# First32.net
KiCad netlist of a schematic drawn in Altium Designer
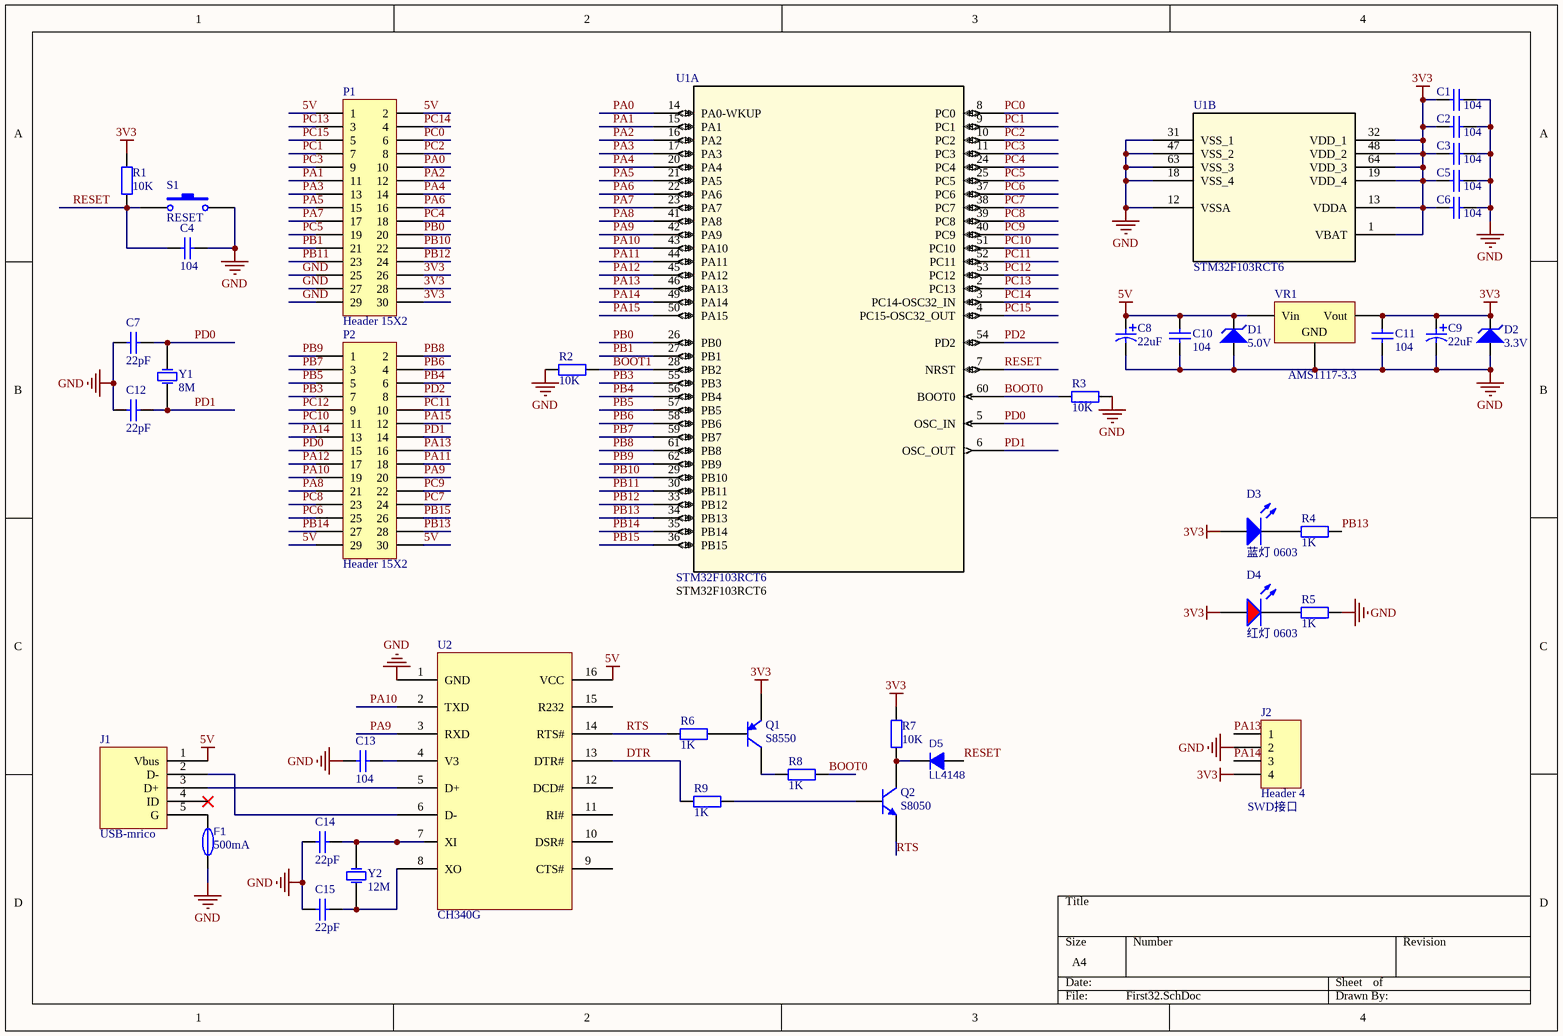
[diagram p0: First32.SchDoc]

(export (version "E")
  (design (tool "Eeschema 10.0.6"))
  (components
    (comp (ref "C1")
      (value "104")
      (footprint "0603_C")
      (description "贴片电容")
      (fields (field (name "Comment") "100nF (104) 10% 50V"))
      (libsource (lib "First32") (part "0603 100nF (104) 10% 50V"))
    )
    (comp (ref "C2")
      (value "104")
      (footprint "0603_C")
      (description "贴片电容")
      (fields (field (name "Comment") "100nF (104) 10% 50V"))
      (libsource (lib "First32") (part "0603 100nF (104) 10% 50V"))
    )
    (comp (ref "C3")
      (value "104")
      (footprint "0603_C")
      (description "贴片电容")
      (fields (field (name "Comment") "100nF (104) 10% 50V"))
      (libsource (lib "First32") (part "0603 100nF (104) 10% 50V"))
    )
    (comp (ref "C4")
      (value "104")
      (footprint "0603_C")
      (description "贴片电容")
      (fields (field (name "Comment") "100nF (104) 10% 50V"))
      (libsource (lib "First32") (part "0603 100nF (104) 10% 50V"))
    )
    (comp (ref "C5")
      (value "104")
      (footprint "0603_C")
      (description "贴片电容")
      (fields (field (name "Comment") "100nF (104) 10% 50V"))
      (libsource (lib "First32") (part "0603 100nF (104) 10% 50V"))
    )
    (comp (ref "C6")
      (value "104")
      (footprint "0603_C")
      (description "贴片电容")
      (fields (field (name "Comment") "100nF (104) 10% 50V"))
      (libsource (lib "First32") (part "0603 100nF (104) 10% 50V"))
    )
    (comp (ref "C7")
      (value "22pF")
      (footprint "0603_C")
      (description "贴片电容")
      (fields (field (name "Comment") "22pF (220) 5% 50V"))
      (libsource (lib "First32") (part "0603 22pF (220) 5% 50V"))
    )
    (comp (ref "C8")
      (value "22uF")
      (footprint "CASE-B_3528")
      (description "钽电容")
      (fields (field (name "Comment") "22uF(226) 10% 16V"))
      (libsource (lib "First32") (part "3528 22uF(226) 10% 16V"))
    )
    (comp (ref "C9")
      (value "22uF")
      (footprint "CASE-B_3528")
      (description "钽电容")
      (fields (field (name "Comment") "22uF(226) 10% 16V"))
      (libsource (lib "First32") (part "3528 22uF(226) 10% 16V"))
    )
    (comp (ref "C10")
      (value "104")
      (footprint "0603_C")
      (description "贴片电容")
      (fields (field (name "Comment") "100nF (104) 10% 50V"))
      (libsource (lib "First32") (part "0603 100nF (104) 10% 50V"))
    )
    (comp (ref "C11")
      (value "104")
      (footprint "0603_C")
      (description "贴片电容")
      (fields (field (name "Comment") "100nF (104) 10% 50V"))
      (libsource (lib "First32") (part "0603 100nF (104) 10% 50V"))
    )
    (comp (ref "C12")
      (value "22pF")
      (footprint "0603_C")
      (description "贴片电容")
      (fields (field (name "Comment") "22pF (220) 5% 50V"))
      (libsource (lib "First32") (part "0603 22pF (220) 5% 50V"))
    )
    (comp (ref "C13")
      (value "104")
      (footprint "0603_C")
      (description "贴片电容")
      (fields (field (name "Comment") "100nF (104) 10% 50V"))
      (libsource (lib "First32") (part "0603 100nF (104) 10% 50V"))
    )
    (comp (ref "C14")
      (value "22pF")
      (footprint "0603_C")
      (description "贴片电容")
      (fields (field (name "Comment") "22pF (220) 5% 50V"))
      (libsource (lib "First32") (part "0603 22pF (220) 5% 50V"))
    )
    (comp (ref "C15")
      (value "22pF")
      (footprint "0603_C")
      (description "贴片电容")
      (fields (field (name "Comment") "22pF (220) 5% 50V"))
      (libsource (lib "First32") (part "0603 22pF (220) 5% 50V"))
    )
    (comp (ref "D1")
      (value "5.0V")
      (footprint "SOD-123")
      (description "稳压二极管")
      (fields (field (name "Comment") "5V"))
      (libsource (lib "First32") (part "Diode-Zener"))
    )
    (comp (ref "D2")
      (value "3.3V")
      (footprint "SOD-123")
      (description "稳压二极管")
      (fields (field (name "Comment") "5V"))
      (libsource (lib "First32") (part "Diode-Zener"))
    )
    (comp (ref "D3")
      (value "蓝灯 0603")
      (footprint "0603_LED")
      (description "发光二极管")
      (libsource (lib "First32") (part "0603 蓝灯"))
    )
    (comp (ref "D4")
      (value "红灯 0603")
      (footprint "0603_LED")
      (description "发光二极管")
      (libsource (lib "First32") (part "0603 红灯"))
    )
    (comp (ref "D5")
      (value "LL4148")
      (footprint "LL-34")
      (fields (field (name "BOM_SUPPLIER PART") "C9808"))
      (libsource (lib "First32") (part "LL4148"))
    )
    (comp (ref "F1")
      (value "500mA")
      (footprint "0805_F")
      (description "保险")
      (fields
        (field (name "BOM_SUPPLIER PART") "C261942")
        (field (name "BOM_MANUFACTURER PART") "TLC-PSMD050")
        (field (name "CONTRIBUTOR") "LCSC")
      )
      (libsource (lib "First32") (part "Fuse"))
    )
    (comp (ref "J1")
      (value "USB-mrico")
      (footprint "SMD-USB-micro_B")
      (libsource (lib "First32") (part "Micro_USB_B"))
    )
    (comp (ref "J2")
      (value "Header 4")
      (footprint "HDR 1X4")
      (description "Header, 4-Pin")
      (fields (field (name "ALTIUM_VALUE") "SWD接口") (field (name "PUBLISHER") "Altium Limited"))
      (libsource (lib "First32") (part "Header 4"))
    )
    (comp (ref "P1")
      (value "Header 15X2")
      (footprint "HDR 2x15 2.54 mm")
      (description "Header, 15-Pin, Dual row")
      (fields (field (name "PUBLISHER") "Altium Limited"))
      (libsource (lib "First32") (part "Header 15X2"))
    )
    (comp (ref "P2")
      (value "Header 15X2")
      (footprint "HDR 2x15 2.54 mm")
      (description "Header, 15-Pin, Dual row")
      (fields (field (name "PUBLISHER") "Altium Limited"))
      (libsource (lib "First32") (part "Header 15X2"))
    )
    (comp (ref "Q1")
      (value "S8550")
      (footprint "SOT-23")
      (description "PNP三极管")
      (fields (field (name "PUBLISHER") "Altium Limited"))
      (libsource (lib "First32") (part "S8550"))
    )
    (comp (ref "Q2")
      (value "S8050")
      (footprint "SOT-23")
      (description "NPN三极管")
      (libsource (lib "First32") (part "S8050"))
    )
    (comp (ref "R1")
      (value "10K")
      (footprint "0603_R")
      (description "贴片电阻")
      (libsource (lib "First32") (part "0603 10KΩ (1002) 1%"))
    )
    (comp (ref "R2")
      (value "10K")
      (footprint "0603_R")
      (description "贴片电阻")
      (libsource (lib "") (part "0603 10KΩ (1002) 1%_2"))
    )
    (comp (ref "R3")
      (value "10K")
      (footprint "0603_R")
      (description "贴片电阻")
      (libsource (lib "") (part "0603 10KΩ (1002) 1%_1"))
    )
    (comp (ref "R4")
      (value "1K")
      (footprint "0603_R")
      (description "贴片电阻")
      (libsource (lib "First32") (part "0603 1KΩ (1K) 1%"))
    )
    (comp (ref "R5")
      (value "1K")
      (footprint "0603_R")
      (description "贴片电阻")
      (libsource (lib "First32") (part "0603 1KΩ (1K) 1%"))
    )
    (comp (ref "R6")
      (value "1K")
      (footprint "0603_R")
      (description "贴片电阻")
      (libsource (lib "First32") (part "0603 1KΩ (1K) 1%"))
    )
    (comp (ref "R7")
      (value "10K")
      (footprint "0603_R")
      (description "贴片电阻")
      (libsource (lib "First32") (part "0603 10KΩ (1002) 1%"))
    )
    (comp (ref "R8")
      (value "1K")
      (footprint "0603_R")
      (description "贴片电阻")
      (libsource (lib "First32") (part "0603 1KΩ (1K) 1%"))
    )
    (comp (ref "R9")
      (value "1K")
      (footprint "0603_R")
      (description "贴片电阻")
      (libsource (lib "First32") (part "0603 1KΩ (1K) 1%"))
    )
    (comp (ref "S1")
      (value "RESET")
      (footprint "SW-SMD-4*4")
      (description "4脚按键")
      (fields (field (name "PUBLISHER") "LC"))
      (libsource (lib "First32") (part "SW-PB-4P"))
    )
    (comp (ref "U1")
      (value "STM32F103RCT6")
      (footprint "LQFP64-10x10mm")
      (description "No Description Available")
      (fields
        (field (name "MANUFACTURER_PART_NUMBER") "STM32F103RCT6")
        (field (name "COPYRIGHT") "Copyright (C) 2018 Accelerated Designs. All rights reserved")
      )
      (libsource (lib "First32") (part "STM32F103RCT6"))
    )
    (comp (ref "U2") (value "CH340G") (footprint "SOP-16_150mil") (libsource (lib "First32") (part "CH340G")))
    (comp (ref "VR1")
      (value "AMS1117-3.3")
      (footprint "SOT-223")
      (description "低压差线性稳压(LDO)")
      (libsource (lib "First32") (part "SOT-223 AMS1117-3.3"))
    )
    (comp (ref "Y1")
      (value "8M")
      (footprint "HC-49SMD")
      (description "Crystal Oscillator")
      (fields (field (name "Comment") "XTAL") (field (name "PUBLISHER") "Altium Limited"))
      (libsource (lib "First32") (part "XTAL"))
    )
    (comp (ref "Y2")
      (value "12M")
      (footprint "HC-49S_L11.4-W4.8")
      (description "Crystal Oscillator")
      (fields (field (name "Comment") "XTAL") (field (name "PUBLISHER") "Altium Limited"))
      (libsource (lib "First32") (part "XTAL_12M"))
    )
  )
  (nets
    (net (code "1") (name "/BOOT0") (class "Default")
      (node (ref "R3") (pin "2") (pinfunction "2_2") (pintype "passive"))
      (node (ref "R8") (pin "2") (pinfunction "2_2") (pintype "passive"))
      (node (ref "U1") (pin "60") (pinfunction "BOOT0_60") (pintype "input"))
    )
    (net (code "2") (name "/BOOT1") (class "Default")
      (node (ref "R2") (pin "2") (pinfunction "2_2") (pintype "passive"))
      (node (ref "U1") (pin "28") (pinfunction "PB2_28") (pintype "bidirectional"))
    )
    (net (code "3") (name "/DTR") (class "Default")
      (node (ref "R9") (pin "1") (pinfunction "1_1") (pintype "passive"))
      (node (ref "U2") (pin "13") (pinfunction "DTR#_13") (pintype "passive"))
    )
    (net (code "4") (name "/PA0") (class "Default")
      (node (ref "P1") (pin "10") (pinfunction "10_10") (pintype "passive"))
      (node (ref "U1") (pin "14") (pinfunction "PA0-WKUP_14") (pintype "bidirectional"))
    )
    (net (code "5") (name "/PA1") (class "Default")
      (node (ref "P1") (pin "11") (pinfunction "11_11") (pintype "passive"))
      (node (ref "U1") (pin "15") (pinfunction "PA1_15") (pintype "bidirectional"))
    )
    (net (code "6") (name "/PA2") (class "Default")
      (node (ref "P1") (pin "12") (pinfunction "12_12") (pintype "passive"))
      (node (ref "U1") (pin "16") (pinfunction "PA2_16") (pintype "bidirectional"))
    )
    (net (code "7") (name "/PA3") (class "Default")
      (node (ref "P1") (pin "13") (pinfunction "13_13") (pintype "passive"))
      (node (ref "U1") (pin "17") (pinfunction "PA3_17") (pintype "bidirectional"))
    )
    (net (code "8") (name "/PA4") (class "Default")
      (node (ref "P1") (pin "14") (pinfunction "14_14") (pintype "passive"))
      (node (ref "U1") (pin "20") (pinfunction "PA4_20") (pintype "bidirectional"))
    )
    (net (code "9") (name "/PA5") (class "Default")
      (node (ref "P1") (pin "15") (pinfunction "15_15") (pintype "passive"))
      (node (ref "U1") (pin "21") (pinfunction "PA5_21") (pintype "bidirectional"))
    )
    (net (code "10") (name "/PA6") (class "Default")
      (node (ref "P1") (pin "16") (pinfunction "16_16") (pintype "passive"))
      (node (ref "U1") (pin "22") (pinfunction "PA6_22") (pintype "bidirectional"))
    )
    (net (code "11") (name "/PA7") (class "Default")
      (node (ref "P1") (pin "17") (pinfunction "17_17") (pintype "passive"))
      (node (ref "U1") (pin "23") (pinfunction "PA7_23") (pintype "bidirectional"))
    )
    (net (code "12") (name "/PA8") (class "Default")
      (node (ref "P2") (pin "21") (pinfunction "21_21") (pintype "passive"))
      (node (ref "U1") (pin "41") (pinfunction "PA8_41") (pintype "bidirectional"))
    )
    (net (code "13") (name "/PA9") (class "Default")
      (node (ref "P2") (pin "20") (pinfunction "20_20") (pintype "passive"))
      (node (ref "U1") (pin "42") (pinfunction "PA9_42") (pintype "bidirectional"))
      (node (ref "U2") (pin "3") (pinfunction "RXD_3") (pintype "passive"))
    )
    (net (code "14") (name "/PA10") (class "Default")
      (node (ref "P2") (pin "19") (pinfunction "19_19") (pintype "passive"))
      (node (ref "U1") (pin "43") (pinfunction "PA10_43") (pintype "bidirectional"))
      (node (ref "U2") (pin "2") (pinfunction "TXD_2") (pintype "passive"))
    )
    (net (code "15") (name "/PA11") (class "Default")
      (node (ref "P2") (pin "18") (pinfunction "18_18") (pintype "passive"))
      (node (ref "U1") (pin "44") (pinfunction "PA11_44") (pintype "bidirectional"))
    )
    (net (code "16") (name "/PA12") (class "Default")
      (node (ref "P2") (pin "17") (pinfunction "17_17") (pintype "passive"))
      (node (ref "U1") (pin "45") (pinfunction "PA12_45") (pintype "bidirectional"))
    )
    (net (code "17") (name "/PA13") (class "Default")
      (node (ref "J2") (pin "1") (pinfunction "1_1") (pintype "passive"))
      (node (ref "P2") (pin "16") (pinfunction "16_16") (pintype "passive"))
      (node (ref "U1") (pin "46") (pinfunction "PA13_46") (pintype "bidirectional"))
    )
    (net (code "18") (name "/PA14") (class "Default")
      (node (ref "J2") (pin "3") (pinfunction "3_3") (pintype "passive"))
      (node (ref "P2") (pin "13") (pinfunction "13_13") (pintype "passive"))
      (node (ref "U1") (pin "49") (pinfunction "PA14_49") (pintype "bidirectional"))
    )
    (net (code "19") (name "/PA15") (class "Default")
      (node (ref "P2") (pin "12") (pinfunction "12_12") (pintype "passive"))
      (node (ref "U1") (pin "50") (pinfunction "PA15_50") (pintype "bidirectional"))
    )
    (net (code "20") (name "/PB0") (class "Default")
      (node (ref "P1") (pin "20") (pinfunction "20_20") (pintype "passive"))
      (node (ref "U1") (pin "26") (pinfunction "PB0_26") (pintype "bidirectional"))
    )
    (net (code "21") (name "/PB1") (class "Default")
      (node (ref "P1") (pin "21") (pinfunction "21_21") (pintype "passive"))
      (node (ref "U1") (pin "27") (pinfunction "PB1_27") (pintype "bidirectional"))
    )
    (net (code "22") (name "/PB3") (class "Default")
      (node (ref "P2") (pin "7") (pinfunction "7_7") (pintype "passive"))
      (node (ref "U1") (pin "55") (pinfunction "PB3_55") (pintype "bidirectional"))
    )
    (net (code "23") (name "/PB4") (class "Default")
      (node (ref "P2") (pin "6") (pinfunction "6_6") (pintype "passive"))
      (node (ref "U1") (pin "56") (pinfunction "PB4_56") (pintype "bidirectional"))
    )
    (net (code "24") (name "/PB5") (class "Default")
      (node (ref "P2") (pin "5") (pinfunction "5_5") (pintype "passive"))
      (node (ref "U1") (pin "57") (pinfunction "PB5_57") (pintype "bidirectional"))
    )
    (net (code "25") (name "/PB6") (class "Default")
      (node (ref "P2") (pin "4") (pinfunction "4_4") (pintype "passive"))
      (node (ref "U1") (pin "58") (pinfunction "PB6_58") (pintype "bidirectional"))
    )
    (net (code "26") (name "/PB7") (class "Default")
      (node (ref "P2") (pin "3") (pinfunction "3_3") (pintype "passive"))
      (node (ref "U1") (pin "59") (pinfunction "PB7_59") (pintype "bidirectional"))
    )
    (net (code "27") (name "/PB8") (class "Default")
      (node (ref "P2") (pin "2") (pinfunction "2_2") (pintype "passive"))
      (node (ref "U1") (pin "61") (pinfunction "PB8_61") (pintype "bidirectional"))
    )
    (net (code "28") (name "/PB9") (class "Default")
      (node (ref "P2") (pin "1") (pinfunction "1_1") (pintype "passive"))
      (node (ref "U1") (pin "62") (pinfunction "PB9_62") (pintype "bidirectional"))
    )
    (net (code "29") (name "/PB10") (class "Default")
      (node (ref "P1") (pin "22") (pinfunction "22_22") (pintype "passive"))
      (node (ref "U1") (pin "29") (pinfunction "PB10_29") (pintype "bidirectional"))
    )
    (net (code "30") (name "/PB11") (class "Default")
      (node (ref "P1") (pin "23") (pinfunction "23_23") (pintype "passive"))
      (node (ref "U1") (pin "30") (pinfunction "PB11_30") (pintype "bidirectional"))
    )
    (net (code "31") (name "/PB12") (class "Default")
      (node (ref "P1") (pin "24") (pinfunction "24_24") (pintype "passive"))
      (node (ref "U1") (pin "33") (pinfunction "PB12_33") (pintype "bidirectional"))
    )
    (net (code "32") (name "/PB13") (class "Default")
      (node (ref "P2") (pin "28") (pinfunction "28_28") (pintype "passive"))
      (node (ref "R4") (pin "2") (pinfunction "2_2") (pintype "passive"))
      (node (ref "U1") (pin "34") (pinfunction "PB13_34") (pintype "bidirectional"))
    )
    (net (code "33") (name "/PB14") (class "Default")
      (node (ref "P2") (pin "27") (pinfunction "27_27") (pintype "passive"))
      (node (ref "U1") (pin "35") (pinfunction "PB14_35") (pintype "bidirectional"))
    )
    (net (code "34") (name "/PB15") (class "Default")
      (node (ref "P2") (pin "26") (pinfunction "26_26") (pintype "passive"))
      (node (ref "U1") (pin "36") (pinfunction "PB15_36") (pintype "bidirectional"))
    )
    (net (code "35") (name "/PC0") (class "Default")
      (node (ref "P1") (pin "6") (pinfunction "6_6") (pintype "passive"))
      (node (ref "U1") (pin "8") (pinfunction "PC0_8") (pintype "bidirectional"))
    )
    (net (code "36") (name "/PC1") (class "Default")
      (node (ref "P1") (pin "7") (pinfunction "7_7") (pintype "passive"))
      (node (ref "U1") (pin "9") (pinfunction "PC1_9") (pintype "bidirectional"))
    )
    (net (code "37") (name "/PC2") (class "Default")
      (node (ref "P1") (pin "8") (pinfunction "8_8") (pintype "passive"))
      (node (ref "U1") (pin "10") (pinfunction "PC2_10") (pintype "bidirectional"))
    )
    (net (code "38") (name "/PC3") (class "Default")
      (node (ref "P1") (pin "9") (pinfunction "9_9") (pintype "passive"))
      (node (ref "U1") (pin "11") (pinfunction "PC3_11") (pintype "bidirectional"))
    )
    (net (code "39") (name "/PC4") (class "Default")
      (node (ref "P1") (pin "18") (pinfunction "18_18") (pintype "passive"))
      (node (ref "U1") (pin "24") (pinfunction "PC4_24") (pintype "bidirectional"))
    )
    (net (code "40") (name "/PC5") (class "Default")
      (node (ref "P1") (pin "19") (pinfunction "19_19") (pintype "passive"))
      (node (ref "U1") (pin "25") (pinfunction "PC5_25") (pintype "bidirectional"))
    )
    (net (code "41") (name "/PC6") (class "Default")
      (node (ref "P2") (pin "25") (pinfunction "25_25") (pintype "passive"))
      (node (ref "U1") (pin "37") (pinfunction "PC6_37") (pintype "bidirectional"))
    )
    (net (code "42") (name "/PC7") (class "Default")
      (node (ref "P2") (pin "24") (pinfunction "24_24") (pintype "passive"))
      (node (ref "U1") (pin "38") (pinfunction "PC7_38") (pintype "bidirectional"))
    )
    (net (code "43") (name "/PC8") (class "Default")
      (node (ref "P2") (pin "23") (pinfunction "23_23") (pintype "passive"))
      (node (ref "U1") (pin "39") (pinfunction "PC8_39") (pintype "bidirectional"))
    )
    (net (code "44") (name "/PC9") (class "Default")
      (node (ref "P2") (pin "22") (pinfunction "22_22") (pintype "passive"))
      (node (ref "U1") (pin "40") (pinfunction "PC9_40") (pintype "bidirectional"))
    )
    (net (code "45") (name "/PC10") (class "Default")
      (node (ref "P2") (pin "11") (pinfunction "11_11") (pintype "passive"))
      (node (ref "U1") (pin "51") (pinfunction "PC10_51") (pintype "bidirectional"))
    )
    (net (code "46") (name "/PC11") (class "Default")
      (node (ref "P2") (pin "10") (pinfunction "10_10") (pintype "passive"))
      (node (ref "U1") (pin "52") (pinfunction "PC11_52") (pintype "bidirectional"))
    )
    (net (code "47") (name "/PC12") (class "Default")
      (node (ref "P2") (pin "9") (pinfunction "9_9") (pintype "passive"))
      (node (ref "U1") (pin "53") (pinfunction "PC12_53") (pintype "bidirectional"))
    )
    (net (code "48") (name "/PC13") (class "Default")
      (node (ref "P1") (pin "3") (pinfunction "3_3") (pintype "passive"))
      (node (ref "U1") (pin "2") (pinfunction "PC13_2") (pintype "bidirectional"))
    )
    (net (code "49") (name "/PC14") (class "Default")
      (node (ref "P1") (pin "4") (pinfunction "4_4") (pintype "passive"))
      (node (ref "U1") (pin "3") (pinfunction "PC14-OSC32_IN_3") (pintype "bidirectional"))
    )
    (net (code "50") (name "/PC15") (class "Default")
      (node (ref "P1") (pin "5") (pinfunction "5_5") (pintype "passive"))
      (node (ref "U1") (pin "4") (pinfunction "PC15-OSC32_OUT_4") (pintype "bidirectional"))
    )
    (net (code "51") (name "/PD0") (class "Default")
      (node (ref "C7") (pin "2") (pinfunction "2_2") (pintype "passive"))
      (node (ref "P2") (pin "15") (pinfunction "15_15") (pintype "passive"))
      (node (ref "U1") (pin "5") (pinfunction "OSC_IN_5") (pintype "input"))
      (node (ref "Y1") (pin "2") (pinfunction "OSC2_2") (pintype "passive"))
    )
    (net (code "52") (name "/PD1") (class "Default")
      (node (ref "C12") (pin "2") (pinfunction "2_2") (pintype "passive"))
      (node (ref "P2") (pin "14") (pinfunction "14_14") (pintype "passive"))
      (node (ref "U1") (pin "6") (pinfunction "OSC_OUT_6") (pintype "output"))
      (node (ref "Y1") (pin "1") (pinfunction "OSC1_1") (pintype "passive"))
    )
    (net (code "53") (name "/PD2") (class "Default")
      (node (ref "P2") (pin "8") (pinfunction "8_8") (pintype "passive"))
      (node (ref "U1") (pin "54") (pinfunction "PD2_54") (pintype "bidirectional"))
    )
    (net (code "54") (name "/RESET") (class "Default")
      (node (ref "C4") (pin "1") (pinfunction "1_1") (pintype "passive"))
      (node (ref "D5") (pin "1") (pinfunction "A_1") (pintype "passive"))
      (node (ref "R1") (pin "1") (pinfunction "1_1") (pintype "passive"))
      (node (ref "S1") (pin "1") (pinfunction "1_1") (pintype "passive"))
      (node (ref "U1") (pin "7") (pinfunction "NRST_7") (pintype "bidirectional"))
    )
    (net (code "55") (name "/RTS") (class "Default")
      (node (ref "Q2") (pin "2") (pinfunction "E_2") (pintype "passive"))
      (node (ref "R6") (pin "1") (pinfunction "1_1") (pintype "passive"))
      (node (ref "U2") (pin "14") (pinfunction "RTS#_14") (pintype "passive"))
    )
    (net (code "56") (name "3V3") (class "Default")
      (node (ref "C1") (pin "1") (pinfunction "1_1") (pintype "passive"))
      (node (ref "C11") (pin "1") (pinfunction "1_1") (pintype "passive"))
      (node (ref "C2") (pin "1") (pinfunction "1_1") (pintype "passive"))
      (node (ref "C3") (pin "1") (pinfunction "1_1") (pintype "passive"))
      (node (ref "C5") (pin "1") (pinfunction "1_1") (pintype "passive"))
      (node (ref "C6") (pin "1") (pinfunction "1_1") (pintype "passive"))
      (node (ref "C9") (pin "1") (pinfunction "1_1") (pintype "passive"))
      (node (ref "D2") (pin "1") (pinfunction "K_1") (pintype "passive"))
      (node (ref "D3") (pin "A") (pinfunction "A_A") (pintype "passive"))
      (node (ref "D4") (pin "A") (pinfunction "A_A") (pintype "passive"))
      (node (ref "J2") (pin "4") (pinfunction "4_4") (pintype "passive"))
      (node (ref "P1") (pin "26") (pinfunction "26_26") (pintype "passive"))
      (node (ref "P1") (pin "28") (pinfunction "28_28") (pintype "passive"))
      (node (ref "P1") (pin "30") (pinfunction "30_30") (pintype "passive"))
      (node (ref "Q1") (pin "2") (pinfunction "E_2") (pintype "passive"))
      (node (ref "R1") (pin "2") (pinfunction "2_2") (pintype "passive"))
      (node (ref "R7") (pin "2") (pinfunction "2_2") (pintype "passive"))
      (node (ref "U1") (pin "1") (pinfunction "VBAT_1") (pintype "power_in"))
      (node (ref "U1") (pin "13") (pinfunction "VDDA_13") (pintype "power_in"))
      (node (ref "U1") (pin "19") (pinfunction "VDD_4_19") (pintype "power_in"))
      (node (ref "U1") (pin "32") (pinfunction "VDD_1_32") (pintype "power_in"))
      (node (ref "U1") (pin "48") (pinfunction "VDD_2_48") (pintype "power_in"))
      (node (ref "U1") (pin "64") (pinfunction "VDD_3_64") (pintype "power_in"))
      (node (ref "VR1") (pin "2") (pinfunction "Vout_2") (pintype "passive"))
    )
    (net (code "57") (name "5V") (class "Default")
      (node (ref "C10") (pin "1") (pinfunction "1_1") (pintype "passive"))
      (node (ref "C8") (pin "1") (pinfunction "1_1") (pintype "passive"))
      (node (ref "D1") (pin "1") (pinfunction "K_1") (pintype "passive"))
      (node (ref "J1") (pin "1") (pinfunction "Vbus_1") (pintype "passive"))
      (node (ref "P1") (pin "1") (pinfunction "1_1") (pintype "passive"))
      (node (ref "P1") (pin "2") (pinfunction "2_2") (pintype "passive"))
      (node (ref "P2") (pin "29") (pinfunction "29_29") (pintype "passive"))
      (node (ref "P2") (pin "30") (pinfunction "30_30") (pintype "passive"))
      (node (ref "U2") (pin "16") (pinfunction "VCC_16") (pintype "passive"))
      (node (ref "VR1") (pin "3") (pinfunction "Vin_3") (pintype "passive"))
    )
    (net (code "58") (name "GND") (class "Default")
      (node (ref "C1") (pin "2") (pinfunction "2_2") (pintype "passive"))
      (node (ref "C10") (pin "2") (pinfunction "2_2") (pintype "passive"))
      (node (ref "C11") (pin "2") (pinfunction "2_2") (pintype "passive"))
      (node (ref "C12") (pin "1") (pinfunction "1_1") (pintype "passive"))
      (node (ref "C13") (pin "1") (pinfunction "1_1") (pintype "passive"))
      (node (ref "C14") (pin "1") (pinfunction "1_1") (pintype "passive"))
      (node (ref "C15") (pin "1") (pinfunction "1_1") (pintype "passive"))
      (node (ref "C2") (pin "2") (pinfunction "2_2") (pintype "passive"))
      (node (ref "C3") (pin "2") (pinfunction "2_2") (pintype "passive"))
      (node (ref "C4") (pin "2") (pinfunction "2_2") (pintype "passive"))
      (node (ref "C5") (pin "2") (pinfunction "2_2") (pintype "passive"))
      (node (ref "C6") (pin "2") (pinfunction "2_2") (pintype "passive"))
      (node (ref "C7") (pin "1") (pinfunction "1_1") (pintype "passive"))
      (node (ref "C8") (pin "2") (pinfunction "2_2") (pintype "passive"))
      (node (ref "C9") (pin "2") (pinfunction "2_2") (pintype "passive"))
      (node (ref "D1") (pin "2") (pinfunction "A_2") (pintype "passive"))
      (node (ref "D2") (pin "2") (pinfunction "A_2") (pintype "passive"))
      (node (ref "F1") (pin "1") (pinfunction "1_1") (pintype "passive"))
      (node (ref "J2") (pin "2") (pinfunction "2_2") (pintype "passive"))
      (node (ref "P1") (pin "25") (pinfunction "25_25") (pintype "passive"))
      (node (ref "P1") (pin "27") (pinfunction "27_27") (pintype "passive"))
      (node (ref "P1") (pin "29") (pinfunction "29_29") (pintype "passive"))
      (node (ref "R2") (pin "1") (pinfunction "1_1") (pintype "passive"))
      (node (ref "R3") (pin "1") (pinfunction "1_1") (pintype "passive"))
      (node (ref "R5") (pin "2") (pinfunction "2_2") (pintype "passive"))
      (node (ref "S1") (pin "2") (pinfunction "2_2") (pintype "passive"))
      (node (ref "U1") (pin "12") (pinfunction "VSSA_12") (pintype "power_in"))
      (node (ref "U1") (pin "18") (pinfunction "VSS_4_18") (pintype "power_in"))
      (node (ref "U1") (pin "31") (pinfunction "VSS_1_31") (pintype "power_in"))
      (node (ref "U1") (pin "47") (pinfunction "VSS_2_47") (pintype "power_in"))
      (node (ref "U1") (pin "63") (pinfunction "VSS_3_63") (pintype "power_in"))
      (node (ref "U2") (pin "1") (pinfunction "GND_1") (pintype "passive"))
      (node (ref "VR1") (pin "1") (pinfunction "GND_1") (pintype "passive"))
    )
    (net (code "59") (name "Net-(D3-PadK)") (class "Default")
      (node (ref "D3") (pin "K") (pinfunction "K_K") (pintype "passive"))
      (node (ref "R4") (pin "1") (pinfunction "1_1") (pintype "passive"))
    )
    (net (code "60") (name "Net-(D4-PadK)") (class "Default")
      (node (ref "D4") (pin "K") (pinfunction "K_K") (pintype "passive"))
      (node (ref "R5") (pin "1") (pinfunction "1_1") (pintype "passive"))
    )
    (net (code "61") (name "Net-(D5-K)") (class "Default")
      (node (ref "D5") (pin "2") (pinfunction "K_2") (pintype "passive"))
      (node (ref "Q2") (pin "3") (pinfunction "C_3") (pintype "passive"))
      (node (ref "R7") (pin "1") (pinfunction "1_1") (pintype "passive"))
    )
    (net (code "62") (name "Net-(J1-D+)") (class "Default")
      (node (ref "J1") (pin "3") (pinfunction "D+_3") (pintype "passive"))
      (node (ref "U2") (pin "5") (pinfunction "D+_5") (pintype "passive"))
    )
    (net (code "63") (name "Net-(J1-D-)") (class "Default")
      (node (ref "J1") (pin "2") (pinfunction "D-_2") (pintype "passive"))
      (node (ref "U2") (pin "6") (pinfunction "D-_6") (pintype "passive"))
    )
    (net (code "64") (name "Net-(J1-G)") (class "Default")
      (node (ref "F1") (pin "2") (pinfunction "2_2") (pintype "passive"))
      (node (ref "J1") (pin "5") (pinfunction "G_5") (pintype "passive"))
    )
    (net (code "65") (name "Net-(Q1-B)") (class "Default")
      (node (ref "Q1") (pin "1") (pinfunction "B_1") (pintype "passive"))
      (node (ref "R6") (pin "2") (pinfunction "2_2") (pintype "passive"))
    )
    (net (code "66") (name "Net-(Q1-C)") (class "Default")
      (node (ref "Q1") (pin "3") (pinfunction "C_3") (pintype "passive"))
      (node (ref "R8") (pin "1") (pinfunction "1_1") (pintype "passive"))
    )
    (net (code "67") (name "Net-(Q2-B)") (class "Default")
      (node (ref "Q2") (pin "1") (pinfunction "B_1") (pintype "passive"))
      (node (ref "R9") (pin "2") (pinfunction "2_2") (pintype "passive"))
    )
    (net (code "68") (name "Net-(U2-V3)") (class "Default")
      (node (ref "C13") (pin "2") (pinfunction "2_2") (pintype "passive"))
      (node (ref "U2") (pin "4") (pinfunction "V3_4") (pintype "passive"))
    )
    (net (code "69") (name "Net-(U2-XI)") (class "Default")
      (node (ref "C14") (pin "2") (pinfunction "2_2") (pintype "passive"))
      (node (ref "U2") (pin "7") (pinfunction "XI_7") (pintype "passive"))
      (node (ref "Y2") (pin "1") (pinfunction "OSC1_1") (pintype "passive"))
    )
    (net (code "70") (name "Net-(U2-XO)") (class "Default")
      (node (ref "C15") (pin "2") (pinfunction "2_2") (pintype "passive"))
      (node (ref "U2") (pin "8") (pinfunction "XO_8") (pintype "passive"))
      (node (ref "Y2") (pin "2") (pinfunction "OSC2_2") (pintype "passive"))
    )
    (net (code "71") (name "unconnected-(J1-ID-Pad4)") (class "Default")
      (node (ref "J1") (pin "4") (pinfunction "ID_4") (pintype "passive+no_connect"))
    )
    (net (code "72") (name "unconnected-(U2-CTS#-Pad9)") (class "Default")
      (node (ref "U2") (pin "9") (pinfunction "CTS#_9") (pintype "passive"))
    )
    (net (code "73") (name "unconnected-(U2-DCD#-Pad12)") (class "Default")
      (node (ref "U2") (pin "12") (pinfunction "DCD#_12") (pintype "passive"))
    )
    (net (code "74") (name "unconnected-(U2-DSR#-Pad10)") (class "Default")
      (node (ref "U2") (pin "10") (pinfunction "DSR#_10") (pintype "passive"))
    )
    (net (code "75") (name "unconnected-(U2-R232-Pad15)") (class "Default")
      (node (ref "U2") (pin "15") (pinfunction "R232_15") (pintype "passive"))
    )
    (net (code "76") (name "unconnected-(U2-RI#-Pad11)") (class "Default")
      (node (ref "U2") (pin "11") (pinfunction "RI#_11") (pintype "passive"))
    )
  )
)
